# design.net
KiCad netlist of a schematic drawn in Altium Designer
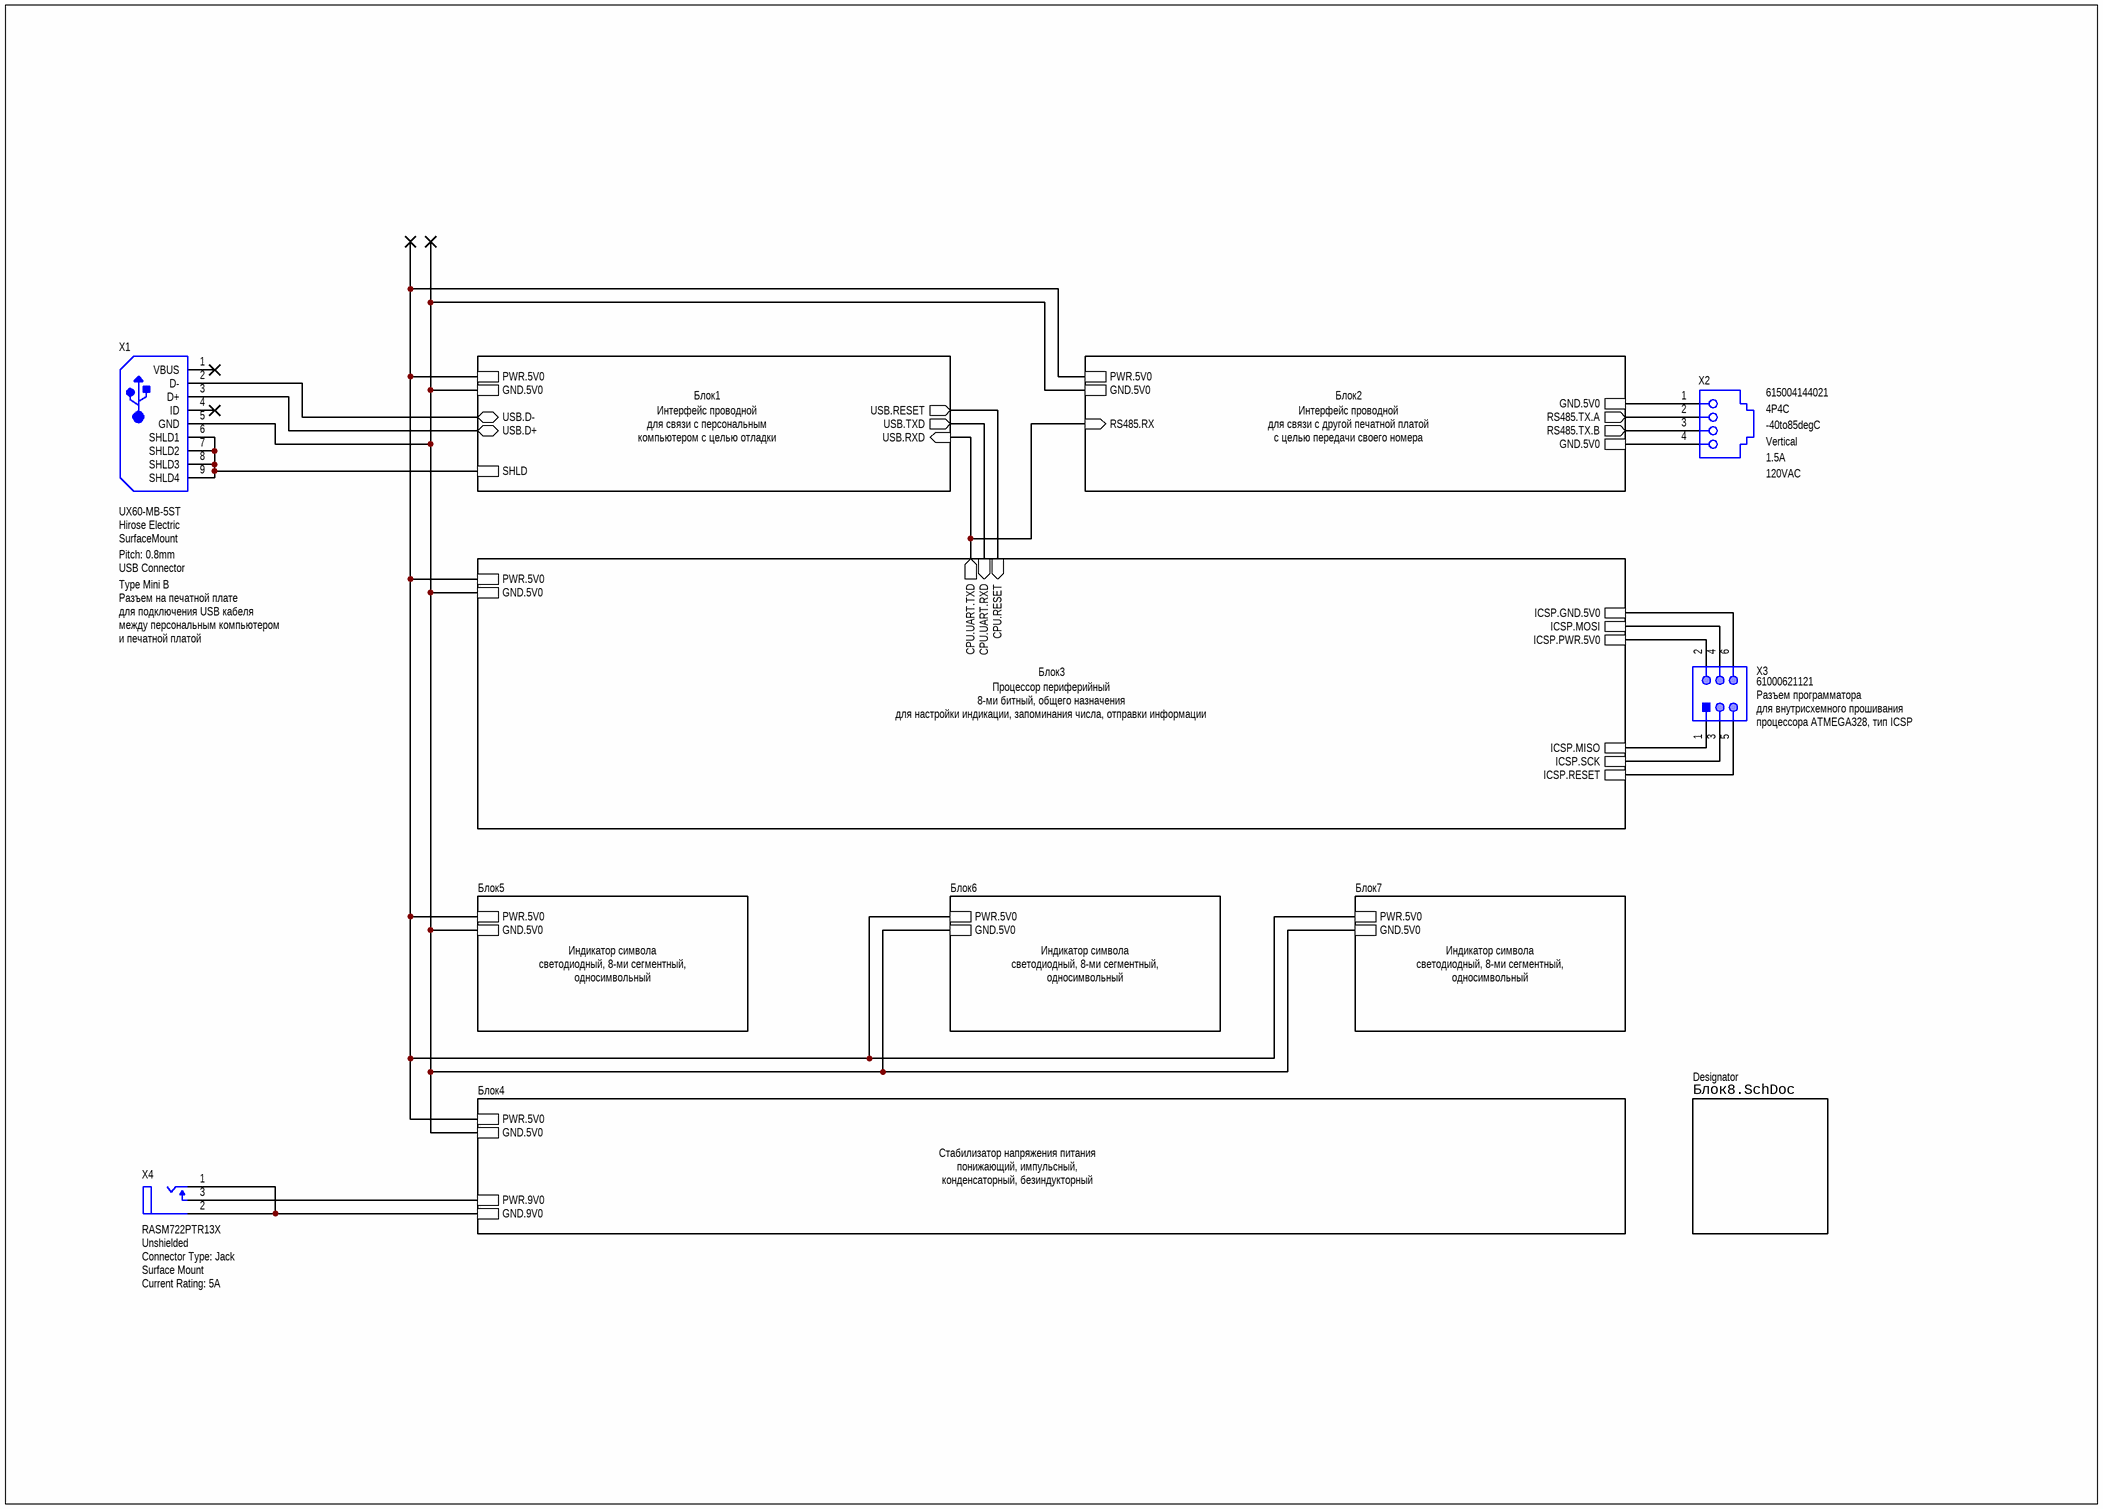
[diagram p0: Структура.SchDoc]

(export (version "E")
  (design (tool "Eeschema 10.0.6"))
  (components
    (comp (ref "X1")
      (value "UX60-MB-5ST")
      (footprint "HIRO-UX60-MB-5ST_V")
      (description "USB Connector Mini B Type, 1 A, 5 V AC, -30 to 75 degC, 5-Pin SMD, RoHS, Tape and Reel")
      (fields
        (field (name "MANUFACTURER") "Hirose Electric")
        (field (name "TERMINATION") "SurfaceMount")
        (field (name "PITCH") "0.8mm")
        (field (name "PARAMETER 1") "USB Connector")
        (field (name "PARAMETER 2") "Type Mini B")
        (field (name "PARAMETER 3") "Разъем на печатной плате")
        (field (name "PARAMETER 4") "для подключения USB кабеля")
        (field (name "PARAMETER 5") "между персональным компьютером")
        (field (name "PARAMETER 6") "и печатной платой")
      )
      (libsource (lib "Altium Content Vault") (part "USB-5-4SHLD"))
    )
    (comp (ref "X2")
      (value "615004144021")
      (footprint "615004144021")
      (description "Modular Jack WR-MJ, Plastic, with Panel Stop, Vertical Entry, THT, 4P4C")
      (fields
        (field (name "PIN NUMBER") "4P4C")
        (field (name "OPERATING TEMPERATURE") "-40to85degC")
        (field (name "ENTRANCE") "Vertical")
        (field (name "RATED CURRENT") "1.5A")
        (field (name "MANUFACTURER") "Wurth Elektronik")
        (field (name "WORKING VOLTAGE") "120VAC")
        (field (name "PUBLISHER") "WurthElektronik")
      )
      (libsource (lib "Altium Content Vault") (part "WE-CN-1P-F-J4_A"))
    )
    (comp (ref "X3")
      (value "61000621121")
      (footprint "61000621121")
      (description "SMT Vertical Pin Header WR-PHD, Pitch 2.54 mm, Dual Row, 6 pins")
      (fields
        (field (name "MANUFACTURER") "Wurth Elektronik")
        (field (name "PARAMETER 1") "Разъем программатора")
        (field (name "PARAMETER 2") "для внутрисхемного прошивания")
        (field (name "PARAMETER 3") "процессора ATMEGA328, тип ICSP")
        (field (name "PUBLISHER") "WurthElektronik")
      )
      (libsource (lib "Altium Content Vault") (part "WE-CN-2P-M-R6"))
    )
    (comp (ref "X4")
      (value "RASM722PTR13X")
      (footprint "FP-RASM722PTR13X-MFG")
      (description "CONN PWR JACK 2.1X5.5MM SOLDER")
      (fields
        (field (name "SHIELDING") "Unshielded")
        (field (name "CONNECTOR TYPE") "Jack")
        (field (name "MOUNT") "Surface Mount")
        (field (name "CURRENT RATING") "5A")
      )
      (libsource (lib "Altium Content Vault") (part "69023cd999ddc70d2a190894d9bbb58"))
    )
  )
  (nets
    (net (code "2") (name "/GND.5V0") (class "Default")
      (node (ref "X2") (pin "4") (pinfunction "4_4") (pintype "passive"))
    )
    (net (code "3") (name "/GND.5V0_1") (class "Default")
      (node (ref "X1") (pin "5") (pinfunction "GND_5") (pintype "power_in+no_connect"))
    )
    (net (code "4") (name "/GND.5V0_2") (class "Default")
      (node (ref "X2") (pin "1") (pinfunction "1_1") (pintype "passive"))
    )
    (net (code "5") (name "/GND.9V0") (class "Default")
      (node (ref "X4") (pin "1") (pinfunction "TIP_TERMINAL(CENTER_PIN)_1") (pintype "passive"))
      (node (ref "X4") (pin "2") (pinfunction "SLEEVE_TERMINAL_2") (pintype "passive"))
    )
    (net (code "6") (name "/ICSP.GND.5V0") (class "Default")
      (node (ref "X3") (pin "6") (pinfunction "6_6") (pintype "passive"))
    )
    (net (code "7") (name "/ICSP.MISO") (class "Default")
      (node (ref "X3") (pin "1") (pinfunction "1_1") (pintype "passive"))
    )
    (net (code "8") (name "/ICSP.MOSI") (class "Default")
      (node (ref "X3") (pin "4") (pinfunction "4_4") (pintype "passive"))
    )
    (net (code "9") (name "/ICSP.PWR.5V0") (class "Default")
      (node (ref "X3") (pin "2") (pinfunction "2_2") (pintype "passive"))
    )
    (net (code "10") (name "/ICSP.RESET") (class "Default")
      (node (ref "X3") (pin "5") (pinfunction "5_5") (pintype "passive"))
    )
    (net (code "11") (name "/ICSP.SCK") (class "Default")
      (node (ref "X3") (pin "3") (pinfunction "3_3") (pintype "passive"))
    )
    (net (code "13") (name "/PWR.9V0") (class "Default")
      (node (ref "X4") (pin "3") (pinfunction "SHUNT_TERMINAL_3") (pintype "passive"))
    )
    (net (code "14") (name "/RS485.TX.A") (class "Default")
      (node (ref "X2") (pin "2") (pinfunction "2_2") (pintype "passive"))
    )
    (net (code "15") (name "/RS485.TX.B") (class "Default")
      (node (ref "X2") (pin "3") (pinfunction "3_3") (pintype "passive"))
    )
    (net (code "16") (name "/SHLD") (class "Default")
      (node (ref "X1") (pin "6") (pinfunction "SHLD1_6") (pintype "passive"))
      (node (ref "X1") (pin "7") (pinfunction "SHLD2_7") (pintype "passive"))
      (node (ref "X1") (pin "8") (pinfunction "SHLD3_8") (pintype "passive"))
      (node (ref "X1") (pin "9") (pinfunction "SHLD4_9") (pintype "passive"))
    )
    (net (code "17") (name "/USB.D+") (class "Default")
      (node (ref "X1") (pin "3") (pinfunction "D+_3") (pintype "passive"))
    )
    (net (code "18") (name "/USB.D-") (class "Default")
      (node (ref "X1") (pin "2") (pinfunction "D-_2") (pintype "passive"))
    )
    (net (code "21") (name "unconnected-(X1-ID-Pad4)") (class "Default")
      (node (ref "X1") (pin "4") (pinfunction "ID_4") (pintype "passive+no_connect"))
    )
    (net (code "22") (name "unconnected-(X1-VBUS-Pad1)") (class "Default")
      (node (ref "X1") (pin "1") (pinfunction "VBUS_1") (pintype "power_in+no_connect"))
    )
  )
)
